# ESP32-XTonUINO.net
KiCad netlist of a schematic drawn in EAGLE
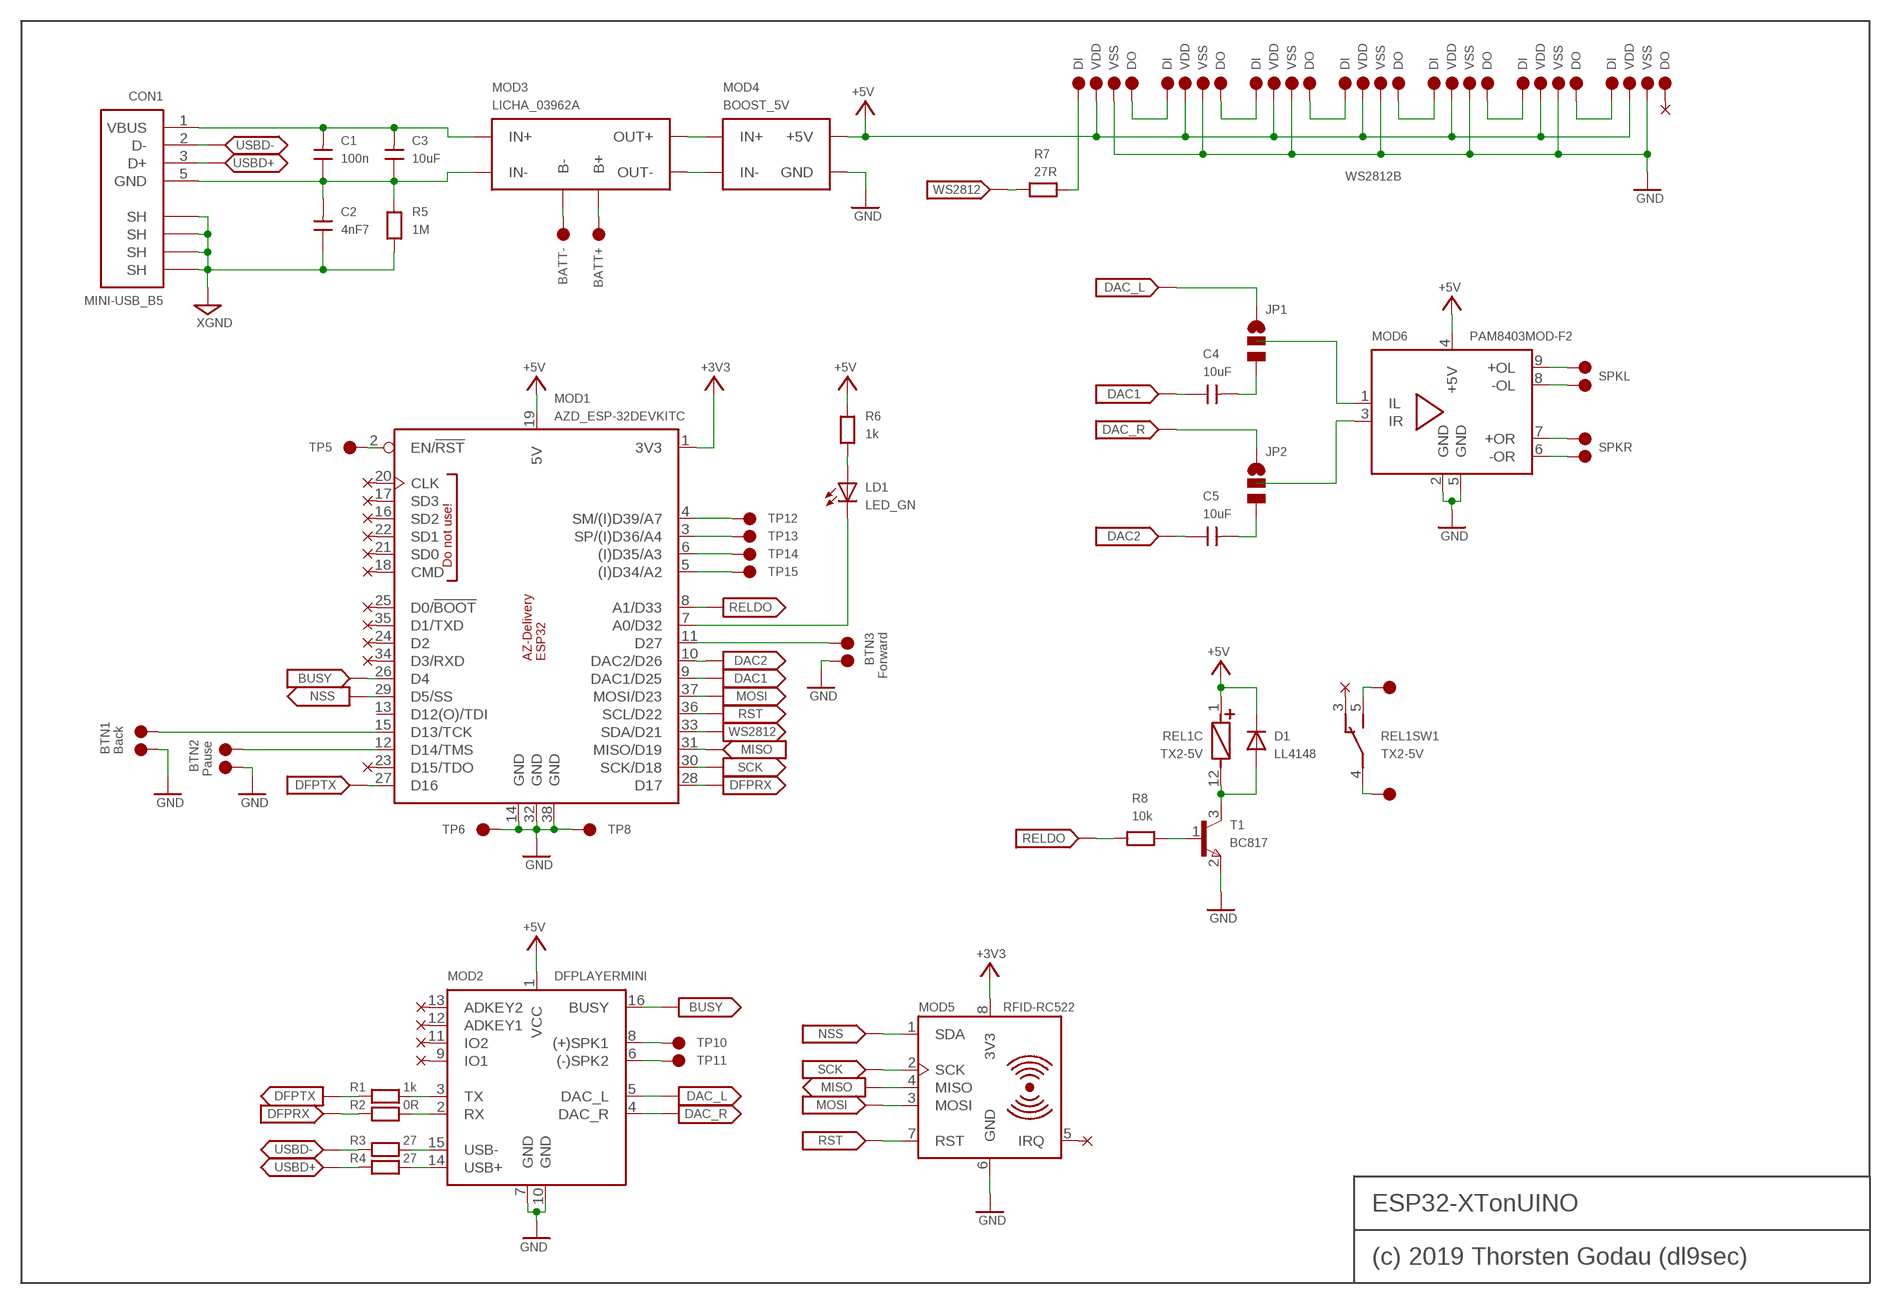
[diagram p0: schematic, sheet 1]

(export (version "E")
  (design (tool "Eeschema 10.0.6"))
  (components
    (comp (ref "C1")
      (value "100n")
      (footprint "eagle-import:0805")
      (libsource (lib "eagle-import") (part "C0805"))
    )
    (comp (ref "C2")
      (value "4nF7")
      (footprint "eagle-import:0805")
      (libsource (lib "eagle-import") (part "C0805"))
    )
    (comp (ref "C3")
      (value "10uF")
      (footprint "eagle-import:0805")
      (libsource (lib "eagle-import") (part "C0805"))
    )
    (comp (ref "C4")
      (value "10uF")
      (footprint "eagle-import:0805")
      (libsource (lib "eagle-import") (part "C0805"))
    )
    (comp (ref "C5")
      (value "10uF")
      (footprint "eagle-import:0805")
      (libsource (lib "eagle-import") (part "C0805"))
    )
    (comp (ref "CON1")
      (value "MINI-USB_B5")
      (footprint "eagle-import:MINIUSB_B5")
      (libsource (lib "eagle-import") (part "MINI-USB_B5"))
    )
    (comp (ref "D1")
      (value "LL4148")
      (footprint "eagle-import:MINIMELF")
      (libsource (lib "eagle-import") (part "LL4148"))
    )
    (comp (ref "JP1")
      (value "JUMPER_1X3SMD")
      (footprint "eagle-import:JUMPER_1X3_SMD")
      (libsource (lib "eagle-import") (part "JUMPER_1X3SMD"))
    )
    (comp (ref "JP2")
      (value "JUMPER_1X3SMD")
      (footprint "eagle-import:JUMPER_1X3_SMD")
      (libsource (lib "eagle-import") (part "JUMPER_1X3SMD"))
    )
    (comp (ref "LD1")
      (value "LED_GN")
      (footprint "eagle-import:LED3MMH")
      (libsource (lib "eagle-import") (part "LED_3MM_GN_H"))
    )
    (comp (ref "MOD1")
      (value "AZD_ESP-32DEVKITC")
      (footprint "eagle-import:AZD_ESP-32DEVKITC")
      (libsource (lib "eagle-import") (part "AZD_ESP-32DEVKITC"))
    )
    (comp (ref "MOD2")
      (value "DFPLAYERMINI")
      (footprint "eagle-import:DFPLAYERMINI")
      (libsource (lib "eagle-import") (part "DFPLAYERMINI"))
    )
    (comp (ref "MOD3")
      (value "LICHA_03962A")
      (footprint "eagle-import:LICHA_03962A")
      (libsource (lib "eagle-import") (part "LICHA_03962A"))
    )
    (comp (ref "MOD4")
      (value "BOOST_5V")
      (footprint "eagle-import:BOOST_5V")
      (libsource (lib "eagle-import") (part "BOOST_5V"))
    )
    (comp (ref "MOD5")
      (value "RFID-RC522")
      (footprint "eagle-import:RFID-RC522")
      (libsource (lib "eagle-import") (part "RFID-RC522"))
    )
    (comp (ref "MOD6")
      (value "PAM8403MOD-F2")
      (footprint "eagle-import:PAM8403MOD2")
      (libsource (lib "eagle-import") (part "PAM8403MOD-F2"))
    )
    (comp (ref "R1")
      (value "1k")
      (footprint "eagle-import:0805")
      (libsource (lib "eagle-import") (part "R0805"))
    )
    (comp (ref "R2")
      (value "0R")
      (footprint "eagle-import:0805")
      (libsource (lib "eagle-import") (part "R0805"))
    )
    (comp (ref "R3")
      (value "27")
      (footprint "eagle-import:0805")
      (libsource (lib "eagle-import") (part "R0805"))
    )
    (comp (ref "R4")
      (value "27")
      (footprint "eagle-import:0805")
      (libsource (lib "eagle-import") (part "R0805"))
    )
    (comp (ref "R5")
      (value "1M")
      (footprint "eagle-import:0805")
      (libsource (lib "eagle-import") (part "R0805"))
    )
    (comp (ref "R6")
      (value "1k")
      (footprint "eagle-import:0805")
      (libsource (lib "eagle-import") (part "R0805"))
    )
    (comp (ref "R7")
      (value "27R")
      (footprint "eagle-import:0805")
      (libsource (lib "eagle-import") (part "R0805"))
    )
    (comp (ref "R8")
      (value "10k")
      (footprint "eagle-import:0805")
      (libsource (lib "eagle-import") (part "R0805"))
    )
    (comp (ref "REL1")
      (value "TX2-5V")
      (footprint "eagle-import:RELTX2")
      (libsource (lib "eagle-import") (part "TX2-5V"))
    )
    (comp (ref "T1")
      (value "BC817")
      (footprint "eagle-import:SOT23")
      (libsource (lib "eagle-import") (part "BTUN"))
    )
    (comp (ref "TP1")
      (value "TESTPINTHT1")
      (footprint "eagle-import:TESTPIN_THT1")
      (libsource (lib "eagle-import") (part "TESTPINTHT1"))
    )
    (comp (ref "TP2")
      (value "TESTPINTHT1")
      (footprint "eagle-import:TESTPIN_THT1")
      (libsource (lib "eagle-import") (part "TESTPINTHT1"))
    )
    (comp (ref "TP3")
      (value "TESTPINTHT1")
      (footprint "eagle-import:TESTPIN_THT1")
      (libsource (lib "eagle-import") (part "TESTPINTHT1"))
    )
    (comp (ref "TP4")
      (value "TESTPINTHT1")
      (footprint "eagle-import:TESTPIN_THT1")
      (libsource (lib "eagle-import") (part "TESTPINTHT1"))
    )
    (comp (ref "TP5")
      (value "TESTPINTHT1")
      (footprint "eagle-import:TESTPIN_THT1")
      (libsource (lib "eagle-import") (part "TESTPINTHT1"))
    )
    (comp (ref "TP6")
      (value "TESTPINTHT1")
      (footprint "eagle-import:TESTPIN_THT1")
      (libsource (lib "eagle-import") (part "TESTPINTHT1"))
    )
    (comp (ref "TP7")
      (value "TESTPINTHT1")
      (footprint "eagle-import:TESTPIN_THT1")
      (libsource (lib "eagle-import") (part "TESTPINTHT1"))
    )
    (comp (ref "TP8")
      (value "TESTPINTHT1")
      (footprint "eagle-import:TESTPIN_THT1")
      (libsource (lib "eagle-import") (part "TESTPINTHT1"))
    )
    (comp (ref "TP9")
      (value "TESTPINTHT1")
      (footprint "eagle-import:TESTPIN_THT1")
      (libsource (lib "eagle-import") (part "TESTPINTHT1"))
    )
    (comp (ref "TP10")
      (value "TESTPINTHT2")
      (footprint "eagle-import:TESTPIN_THT2")
      (libsource (lib "eagle-import") (part "TESTPINTHT2"))
    )
    (comp (ref "TP11")
      (value "TESTPINTHT2")
      (footprint "eagle-import:TESTPIN_THT2")
      (libsource (lib "eagle-import") (part "TESTPINTHT2"))
    )
    (comp (ref "TP12")
      (value "TESTPINTHT1")
      (footprint "eagle-import:TESTPIN_THT1")
      (libsource (lib "eagle-import") (part "TESTPINTHT1"))
    )
    (comp (ref "TP13")
      (value "TESTPINTHT1")
      (footprint "eagle-import:TESTPIN_THT1")
      (libsource (lib "eagle-import") (part "TESTPINTHT1"))
    )
    (comp (ref "TP14")
      (value "TESTPINTHT1")
      (footprint "eagle-import:TESTPIN_THT1")
      (libsource (lib "eagle-import") (part "TESTPINTHT1"))
    )
    (comp (ref "TP15")
      (value "TESTPINTHT1")
      (footprint "eagle-import:TESTPIN_THT1")
      (libsource (lib "eagle-import") (part "TESTPINTHT1"))
    )
    (comp (ref "TP16")
      (value "TESTPINTHT1")
      (footprint "eagle-import:TESTPIN_THT1")
      (libsource (lib "eagle-import") (part "TESTPINTHT1"))
    )
    (comp (ref "TP17")
      (value "TESTPINTHT1")
      (footprint "eagle-import:TESTPIN_THT1")
      (libsource (lib "eagle-import") (part "TESTPINTHT1"))
    )
    (comp (ref "TP18")
      (value "TESTPINTHT1")
      (footprint "eagle-import:TESTPIN_THT1")
      (libsource (lib "eagle-import") (part "TESTPINTHT1"))
    )
    (comp (ref "TP19")
      (value "TESTPINTHT1")
      (footprint "eagle-import:TESTPIN_THT1")
      (libsource (lib "eagle-import") (part "TESTPINTHT1"))
    )
    (comp (ref "TP20")
      (value "TESTPINTHT1")
      (footprint "eagle-import:TESTPIN_THT1")
      (libsource (lib "eagle-import") (part "TESTPINTHT1"))
    )
    (comp (ref "TP21")
      (value "TESTPINTHT1")
      (footprint "eagle-import:TESTPIN_THT1")
      (libsource (lib "eagle-import") (part "TESTPINTHT1"))
    )
    (comp (ref "TP22")
      (value "TESTPINTHT1")
      (footprint "eagle-import:TESTPIN_THT1")
      (libsource (lib "eagle-import") (part "TESTPINTHT1"))
    )
    (comp (ref "TP23")
      (value "TESTPINTHT1")
      (footprint "eagle-import:TESTPIN_THT1")
      (libsource (lib "eagle-import") (part "TESTPINTHT1"))
    )
    (comp (ref "TP24")
      (value "TESTPINTHT1")
      (footprint "eagle-import:TESTPIN_THT1")
      (libsource (lib "eagle-import") (part "TESTPINTHT1"))
    )
    (comp (ref "TP25")
      (value "TESTPINTHT1")
      (footprint "eagle-import:TESTPIN_THT1")
      (libsource (lib "eagle-import") (part "TESTPINTHT1"))
    )
    (comp (ref "TP26")
      (value "TESTPINTHT1")
      (footprint "eagle-import:TESTPIN_THT1")
      (libsource (lib "eagle-import") (part "TESTPINTHT1"))
    )
    (comp (ref "TP27")
      (value "TESTPINTHT1")
      (footprint "eagle-import:TESTPIN_THT1")
      (libsource (lib "eagle-import") (part "TESTPINTHT1"))
    )
    (comp (ref "TP28")
      (value "TESTPINTHT1")
      (footprint "eagle-import:TESTPIN_THT1")
      (libsource (lib "eagle-import") (part "TESTPINTHT1"))
    )
    (comp (ref "TP29")
      (value "TESTPINTHT1")
      (footprint "eagle-import:TESTPIN_THT1")
      (libsource (lib "eagle-import") (part "TESTPINTHT1"))
    )
    (comp (ref "TP30")
      (value "TESTPINTHT1")
      (footprint "eagle-import:TESTPIN_THT1")
      (libsource (lib "eagle-import") (part "TESTPINTHT1"))
    )
    (comp (ref "TP31")
      (value "TESTPINTHT1")
      (footprint "eagle-import:TESTPIN_THT1")
      (libsource (lib "eagle-import") (part "TESTPINTHT1"))
    )
    (comp (ref "TP32")
      (value "TESTPINTHT1")
      (footprint "eagle-import:TESTPIN_THT1")
      (libsource (lib "eagle-import") (part "TESTPINTHT1"))
    )
    (comp (ref "TP33")
      (value "TESTPINTHT1")
      (footprint "eagle-import:TESTPIN_THT1")
      (libsource (lib "eagle-import") (part "TESTPINTHT1"))
    )
    (comp (ref "TP34")
      (value "TESTPINTHT1")
      (footprint "eagle-import:TESTPIN_THT1")
      (libsource (lib "eagle-import") (part "TESTPINTHT1"))
    )
    (comp (ref "TP35")
      (value "TESTPINTHT1")
      (footprint "eagle-import:TESTPIN_THT1")
      (libsource (lib "eagle-import") (part "TESTPINTHT1"))
    )
    (comp (ref "TP36")
      (value "TESTPINTHT1")
      (footprint "eagle-import:TESTPIN_THT1")
      (libsource (lib "eagle-import") (part "TESTPINTHT1"))
    )
    (comp (ref "TP37")
      (value "TESTPINTHT1")
      (footprint "eagle-import:TESTPIN_THT1")
      (libsource (lib "eagle-import") (part "TESTPINTHT1"))
    )
    (comp (ref "TP38")
      (value "TESTPINTHT1")
      (footprint "eagle-import:TESTPIN_THT1")
      (libsource (lib "eagle-import") (part "TESTPINTHT1"))
    )
    (comp (ref "TP39")
      (value "TESTPINTHT1")
      (footprint "eagle-import:TESTPIN_THT1")
      (libsource (lib "eagle-import") (part "TESTPINTHT1"))
    )
    (comp (ref "TP40")
      (value "TESTPINTHT1")
      (footprint "eagle-import:TESTPIN_THT1")
      (libsource (lib "eagle-import") (part "TESTPINTHT1"))
    )
    (comp (ref "TP41")
      (value "TESTPINTHT2")
      (footprint "eagle-import:TESTPIN_THT2")
      (libsource (lib "eagle-import") (part "TESTPINTHT2"))
    )
    (comp (ref "TP42")
      (value "TESTPINTHT2")
      (footprint "eagle-import:TESTPIN_THT2")
      (libsource (lib "eagle-import") (part "TESTPINTHT2"))
    )
    (comp (ref "TP43")
      (value "TESTPINTHT2")
      (footprint "eagle-import:TESTPIN_THT2")
      (libsource (lib "eagle-import") (part "TESTPINTHT2"))
    )
    (comp (ref "TP44")
      (value "TESTPINTHT2")
      (footprint "eagle-import:TESTPIN_THT2")
      (libsource (lib "eagle-import") (part "TESTPINTHT2"))
    )
    (comp (ref "TP45")
      (value "TESTPINTHT1")
      (footprint "eagle-import:TESTPIN_THT1")
      (libsource (lib "eagle-import") (part "TESTPINTHT1"))
    )
    (comp (ref "TP46")
      (value "TESTPINTHT2")
      (footprint "eagle-import:TESTPIN_THT2")
      (libsource (lib "eagle-import") (part "TESTPINTHT2"))
    )
    (comp (ref "TP47")
      (value "TESTPINTHT2")
      (footprint "eagle-import:TESTPIN_THT2")
      (libsource (lib "eagle-import") (part "TESTPINTHT2"))
    )
    (comp (ref "TP48")
      (value "TESTPINTHT1")
      (footprint "eagle-import:TESTPIN_THT1")
      (libsource (lib "eagle-import") (part "TESTPINTHT1"))
    )
    (comp (ref "TP49")
      (value "TESTPINTHT1")
      (footprint "eagle-import:TESTPIN_THT1")
      (libsource (lib "eagle-import") (part "TESTPINTHT1"))
    )
    (comp (ref "TP50")
      (value "TESTPINTHT1")
      (footprint "eagle-import:TESTPIN_THT1")
      (libsource (lib "eagle-import") (part "TESTPINTHT1"))
    )
    (comp (ref "TP51")
      (value "TESTPINTHT1")
      (footprint "eagle-import:TESTPIN_THT1")
      (libsource (lib "eagle-import") (part "TESTPINTHT1"))
    )
  )
  (nets
    (net (code "1") (name "+3V3") (class "Default")
      (node (ref "MOD1") (pin "1") (pinfunction "3V3_1") (pintype "passive"))
      (node (ref "MOD5") (pin "8") (pinfunction "3V3_8") (pintype "power_in"))
    )
    (net (code "2") (name "+5V") (class "Default")
      (node (ref "D1") (pin "K") (pinfunction "K_K") (pintype "passive"))
      (node (ref "MOD1") (pin "19") (pinfunction "5V_19") (pintype "power_in"))
      (node (ref "MOD2") (pin "1") (pinfunction "VCC_1") (pintype "power_in"))
      (node (ref "MOD4") (pin "+5V") (pinfunction "+5V_+5V") (pintype "power_in"))
      (node (ref "MOD6") (pin "4") (pinfunction "+5V_4") (pintype "power_in"))
      (node (ref "R6") (pin "2") (pinfunction "2_2") (pintype "passive"))
      (node (ref "REL1") (pin "1") (pinfunction "+_1") (pintype "power_in"))
      (node (ref "TP19") (pin "1") (pinfunction "TP_1") (pintype "passive"))
      (node (ref "TP23") (pin "1") (pinfunction "TP_1") (pintype "passive"))
      (node (ref "TP27") (pin "1") (pinfunction "TP_1") (pintype "passive"))
      (node (ref "TP31") (pin "1") (pinfunction "TP_1") (pintype "passive"))
      (node (ref "TP35") (pin "1") (pinfunction "TP_1") (pintype "passive"))
      (node (ref "TP39") (pin "1") (pinfunction "TP_1") (pintype "passive"))
      (node (ref "TP49") (pin "1") (pinfunction "TP_1") (pintype "passive"))
    )
    (net (code "3") (name "/BUSY") (class "Default")
      (node (ref "MOD1") (pin "26") (pinfunction "D4_26") (pintype "bidirectional"))
      (node (ref "MOD2") (pin "16") (pinfunction "BUSY_16") (pintype "passive"))
    )
    (net (code "4") (name "/DAC1") (class "Default")
      (node (ref "C4") (pin "1") (pinfunction "1_1") (pintype "passive"))
      (node (ref "MOD1") (pin "9") (pinfunction "DAC1/D25_9") (pintype "bidirectional"))
    )
    (net (code "5") (name "/DAC2") (class "Default")
      (node (ref "C5") (pin "1") (pinfunction "1_1") (pintype "passive"))
      (node (ref "MOD1") (pin "10") (pinfunction "DAC2/D26_10") (pintype "bidirectional"))
    )
    (net (code "6") (name "/DAC_L") (class "Default")
      (node (ref "JP1") (pin "1") (pinfunction "1_1") (pintype "passive"))
      (node (ref "MOD2") (pin "5") (pinfunction "DAC_L_5") (pintype "passive"))
    )
    (net (code "7") (name "/DAC_R") (class "Default")
      (node (ref "JP2") (pin "1") (pinfunction "1_1") (pintype "passive"))
      (node (ref "MOD2") (pin "4") (pinfunction "DAC_R_4") (pintype "passive"))
    )
    (net (code "8") (name "/DFPRX") (class "Default")
      (node (ref "MOD1") (pin "28") (pinfunction "D17_28") (pintype "bidirectional"))
      (node (ref "R2") (pin "1") (pinfunction "1_1") (pintype "passive"))
    )
    (net (code "9") (name "/DFPTX") (class "Default")
      (node (ref "MOD1") (pin "27") (pinfunction "D16_27") (pintype "bidirectional"))
      (node (ref "R1") (pin "1") (pinfunction "1_1") (pintype "passive"))
    )
    (net (code "10") (name "/MISO") (class "Default")
      (node (ref "MOD1") (pin "31") (pinfunction "MISO/D19_31") (pintype "bidirectional"))
      (node (ref "MOD5") (pin "4") (pinfunction "MISO_4") (pintype "passive"))
    )
    (net (code "11") (name "/MOSI") (class "Default")
      (node (ref "MOD1") (pin "37") (pinfunction "MOSI/D23_37") (pintype "bidirectional"))
      (node (ref "MOD5") (pin "3") (pinfunction "MOSI_3") (pintype "passive"))
    )
    (net (code "12") (name "/NSS") (class "Default")
      (node (ref "MOD1") (pin "29") (pinfunction "D5/SS_29") (pintype "bidirectional"))
      (node (ref "MOD5") (pin "1") (pinfunction "SDA_1") (pintype "passive"))
    )
    (net (code "13") (name "/RELDO") (class "Default")
      (node (ref "MOD1") (pin "8") (pinfunction "A1/D33_8") (pintype "bidirectional"))
      (node (ref "R8") (pin "1") (pinfunction "1_1") (pintype "passive"))
    )
    (net (code "14") (name "/RST") (class "Default")
      (node (ref "MOD1") (pin "36") (pinfunction "SCL/D22_36") (pintype "bidirectional"))
      (node (ref "MOD5") (pin "7") (pinfunction "RST_7") (pintype "passive"))
    )
    (net (code "15") (name "/SCK") (class "Default")
      (node (ref "MOD1") (pin "30") (pinfunction "SCK/D18_30") (pintype "bidirectional"))
      (node (ref "MOD5") (pin "2") (pinfunction "SCK_2") (pintype "passive"))
    )
    (net (code "16") (name "/USBD+") (class "Default")
      (node (ref "CON1") (pin "3") (pinfunction "D+_3") (pintype "bidirectional"))
      (node (ref "R4") (pin "1") (pinfunction "1_1") (pintype "passive"))
    )
    (net (code "17") (name "/USBD-") (class "Default")
      (node (ref "CON1") (pin "2") (pinfunction "D-_2") (pintype "bidirectional"))
      (node (ref "R3") (pin "1") (pinfunction "1_1") (pintype "passive"))
    )
    (net (code "18") (name "/WS2812") (class "Default")
      (node (ref "MOD1") (pin "33") (pinfunction "SDA/D21_33") (pintype "bidirectional"))
      (node (ref "R7") (pin "1") (pinfunction "1_1") (pintype "passive"))
    )
    (net (code "19") (name "GND") (class "Default")
      (node (ref "MOD1") (pin "14") (pinfunction "GND_14") (pintype "power_in"))
      (node (ref "MOD1") (pin "32") (pinfunction "GND_32") (pintype "power_in"))
      (node (ref "MOD1") (pin "38") (pinfunction "GND_38") (pintype "power_in"))
      (node (ref "MOD2") (pin "10") (pinfunction "GND_10") (pintype "power_in"))
      (node (ref "MOD2") (pin "7") (pinfunction "GND_7") (pintype "power_in"))
      (node (ref "MOD4") (pin "GND") (pinfunction "GND_GND") (pintype "passive"))
      (node (ref "MOD5") (pin "6") (pinfunction "GND_6") (pintype "power_in"))
      (node (ref "MOD6") (pin "2") (pinfunction "GND_2") (pintype "power_in"))
      (node (ref "MOD6") (pin "5") (pinfunction "GND_5") (pintype "power_in"))
      (node (ref "T1") (pin "2") (pinfunction "E_2") (pintype "passive"))
      (node (ref "TP17") (pin "1") (pinfunction "TP_1") (pintype "passive"))
      (node (ref "TP2") (pin "1") (pinfunction "TP_1") (pintype "passive"))
      (node (ref "TP20") (pin "1") (pinfunction "TP_1") (pintype "passive"))
      (node (ref "TP24") (pin "1") (pinfunction "TP_1") (pintype "passive"))
      (node (ref "TP28") (pin "1") (pinfunction "TP_1") (pintype "passive"))
      (node (ref "TP32") (pin "1") (pinfunction "TP_1") (pintype "passive"))
      (node (ref "TP36") (pin "1") (pinfunction "TP_1") (pintype "passive"))
      (node (ref "TP4") (pin "1") (pinfunction "TP_1") (pintype "passive"))
      (node (ref "TP40") (pin "1") (pinfunction "TP_1") (pintype "passive"))
      (node (ref "TP50") (pin "1") (pinfunction "TP_1") (pintype "passive"))
      (node (ref "TP6") (pin "1") (pinfunction "TP_1") (pintype "passive"))
      (node (ref "TP8") (pin "1") (pinfunction "TP_1") (pintype "passive"))
    )
    (net (code "20") (name "Net-(C4-Pad2)") (class "Default")
      (node (ref "C4") (pin "2") (pinfunction "2_2") (pintype "passive"))
      (node (ref "JP1") (pin "3") (pinfunction "3_3") (pintype "passive"))
    )
    (net (code "21") (name "Net-(C5-Pad2)") (class "Default")
      (node (ref "C5") (pin "2") (pinfunction "2_2") (pintype "passive"))
      (node (ref "JP2") (pin "3") (pinfunction "3_3") (pintype "passive"))
    )
    (net (code "22") (name "Net-(CON1-GND)") (class "Default")
      (node (ref "C1") (pin "1") (pinfunction "1_1") (pintype "passive"))
      (node (ref "C2") (pin "2") (pinfunction "2_2") (pintype "passive"))
      (node (ref "C3") (pin "1") (pinfunction "1_1") (pintype "passive"))
      (node (ref "CON1") (pin "5") (pinfunction "GND_5") (pintype "power_in"))
      (node (ref "MOD3") (pin "IN-") (pinfunction "IN-_IN-") (pintype "passive"))
      (node (ref "R5") (pin "2") (pinfunction "2_2") (pintype "passive"))
    )
    (net (code "23") (name "Net-(CON1-VBUS)") (class "Default")
      (node (ref "C1") (pin "2") (pinfunction "2_2") (pintype "passive"))
      (node (ref "C3") (pin "2") (pinfunction "2_2") (pintype "passive"))
      (node (ref "CON1") (pin "1") (pinfunction "VBUS_1") (pintype "power_in"))
      (node (ref "MOD3") (pin "IN+") (pinfunction "IN+_IN+") (pintype "passive"))
    )
    (net (code "24") (name "Net-(LD1-PadA)") (class "Default")
      (node (ref "LD1") (pin "A") (pinfunction "A_A") (pintype "passive"))
      (node (ref "R6") (pin "1") (pinfunction "1_1") (pintype "passive"))
    )
    (net (code "25") (name "Net-(MOD1-(I)D34{slash}A2)") (class "Default")
      (node (ref "MOD1") (pin "5") (pinfunction "(I)D34/A2_5") (pintype "input"))
      (node (ref "TP15") (pin "1") (pinfunction "TP_1") (pintype "passive"))
    )
    (net (code "26") (name "Net-(MOD1-(I)D35{slash}A3)") (class "Default")
      (node (ref "MOD1") (pin "6") (pinfunction "(I)D35/A3_6") (pintype "input"))
      (node (ref "TP14") (pin "1") (pinfunction "TP_1") (pintype "passive"))
    )
    (net (code "27") (name "Net-(MOD1-A0{slash}D32)") (class "Default")
      (node (ref "LD1") (pin "K") (pinfunction "K_K") (pintype "passive"))
      (node (ref "MOD1") (pin "7") (pinfunction "A0/D32_7") (pintype "bidirectional"))
    )
    (net (code "28") (name "Net-(MOD1-D13{slash}TCK)") (class "Default")
      (node (ref "MOD1") (pin "15") (pinfunction "D13/TCK_15") (pintype "bidirectional"))
      (node (ref "TP1") (pin "1") (pinfunction "TP_1") (pintype "passive"))
    )
    (net (code "29") (name "Net-(MOD1-D14{slash}TMS)") (class "Default")
      (node (ref "MOD1") (pin "12") (pinfunction "D14/TMS_12") (pintype "bidirectional"))
      (node (ref "TP3") (pin "1") (pinfunction "TP_1") (pintype "passive"))
    )
    (net (code "30") (name "Net-(MOD1-D27)") (class "Default")
      (node (ref "MOD1") (pin "11") (pinfunction "D27_11") (pintype "bidirectional"))
      (node (ref "TP16") (pin "1") (pinfunction "TP_1") (pintype "passive"))
    )
    (net (code "31") (name "Net-(MOD1-EN{slash}~{RST})") (class "Default")
      (node (ref "MOD1") (pin "2") (pinfunction "EN/~{RST}_2") (pintype "input"))
      (node (ref "TP5") (pin "1") (pinfunction "TP_1") (pintype "passive"))
    )
    (net (code "32") (name "Net-(MOD1-SM{slash}(I)D39{slash}A7)") (class "Default")
      (node (ref "MOD1") (pin "4") (pinfunction "SM/(I)D39/A7_4") (pintype "input"))
      (node (ref "TP12") (pin "1") (pinfunction "TP_1") (pintype "passive"))
    )
    (net (code "33") (name "Net-(MOD1-SP{slash}(I)D36{slash}A4)") (class "Default")
      (node (ref "MOD1") (pin "3") (pinfunction "SP/(I)D36/A4_3") (pintype "input"))
      (node (ref "TP13") (pin "1") (pinfunction "TP_1") (pintype "passive"))
    )
    (net (code "34") (name "Net-(MOD2-(+)SPK1)") (class "Default")
      (node (ref "MOD2") (pin "8") (pinfunction "(+)SPK1_8") (pintype "passive"))
      (node (ref "TP10") (pin "1") (pinfunction "TP_1") (pintype "passive"))
    )
    (net (code "35") (name "Net-(MOD2-(-)SPK2)") (class "Default")
      (node (ref "MOD2") (pin "6") (pinfunction "(-)SPK2_6") (pintype "passive"))
      (node (ref "TP11") (pin "1") (pinfunction "TP_1") (pintype "passive"))
    )
    (net (code "36") (name "Net-(MOD2-RX)") (class "Default")
      (node (ref "MOD2") (pin "2") (pinfunction "RX_2") (pintype "passive"))
      (node (ref "R2") (pin "2") (pinfunction "2_2") (pintype "passive"))
    )
    (net (code "37") (name "Net-(MOD2-TX)") (class "Default")
      (node (ref "MOD2") (pin "3") (pinfunction "TX_3") (pintype "passive"))
      (node (ref "R1") (pin "2") (pinfunction "2_2") (pintype "passive"))
    )
    (net (code "38") (name "Net-(MOD2-USB+)") (class "Default")
      (node (ref "MOD2") (pin "14") (pinfunction "USB+_14") (pintype "passive"))
      (node (ref "R4") (pin "2") (pinfunction "2_2") (pintype "passive"))
    )
    (net (code "39") (name "Net-(MOD2-USB-)") (class "Default")
      (node (ref "MOD2") (pin "15") (pinfunction "USB-_15") (pintype "passive"))
      (node (ref "R3") (pin "2") (pinfunction "2_2") (pintype "passive"))
    )
    (net (code "40") (name "Net-(MOD3-PadOUT+)") (class "Default")
      (node (ref "MOD3") (pin "OUT+") (pinfunction "OUT+_OUT+") (pintype "power_in"))
      (node (ref "MOD4") (pin "IN+") (pinfunction "IN+_IN+") (pintype "passive"))
    )
    (net (code "41") (name "Net-(MOD3-PadOUT-)") (class "Default")
      (node (ref "MOD3") (pin "OUT-") (pinfunction "OUT-_OUT-") (pintype "passive"))
      (node (ref "MOD4") (pin "IN-") (pinfunction "IN-_IN-") (pintype "passive"))
    )
    (net (code "42") (name "Net-(MOD6-+OL)") (class "Default")
      (node (ref "MOD6") (pin "9") (pinfunction "+OL_9") (pintype "passive"))
      (node (ref "TP41") (pin "1") (pinfunction "TP_1") (pintype "passive"))
    )
    (net (code "43") (name "Net-(MOD6-+OR)") (class "Default")
      (node (ref "MOD6") (pin "7") (pinfunction "+OR_7") (pintype "passive"))
      (node (ref "TP43") (pin "1") (pinfunction "TP_1") (pintype "passive"))
    )
    (net (code "44") (name "Net-(MOD6--OL)") (class "Default")
      (node (ref "MOD6") (pin "8") (pinfunction "-OL_8") (pintype "passive"))
      (node (ref "TP42") (pin "1") (pinfunction "TP_1") (pintype "passive"))
    )
    (net (code "45") (name "Net-(MOD6--OR)") (class "Default")
      (node (ref "MOD6") (pin "6") (pinfunction "-OR_6") (pintype "passive"))
      (node (ref "TP44") (pin "1") (pinfunction "TP_1") (pintype "passive"))
    )
    (net (code "46") (name "Net-(MOD6-IL)") (class "Default")
      (node (ref "JP1") (pin "2") (pinfunction "2_2") (pintype "passive"))
      (node (ref "MOD6") (pin "1") (pinfunction "IL_1") (pintype "passive"))
    )
    (net (code "47") (name "Net-(MOD6-IR)") (class "Default")
      (node (ref "JP2") (pin "2") (pinfunction "2_2") (pintype "passive"))
      (node (ref "MOD6") (pin "3") (pinfunction "IR_3") (pintype "passive"))
    )
    (net (code "48") (name "Net-(REL1A--)") (class "Default")
      (node (ref "D1") (pin "A") (pinfunction "A_A") (pintype "passive"))
      (node (ref "REL1") (pin "12") (pinfunction "-_12") (pintype "power_in"))
      (node (ref "T1") (pin "3") (pinfunction "C_3") (pintype "passive"))
    )
    (net (code "49") (name "Net-(REL1B-COM)") (class "Default")
      (node (ref "REL1") (pin "4") (pinfunction "COM_4") (pintype "passive"))
      (node (ref "TP47") (pin "1") (pinfunction "TP_1") (pintype "passive"))
    )
    (net (code "50") (name "Net-(REL1B-NO)") (class "Default")
      (node (ref "REL1") (pin "5") (pinfunction "NO_5") (pintype "passive"))
      (node (ref "TP46") (pin "1") (pinfunction "TP_1") (pintype "passive"))
    )
    (net (code "51") (name "Net-(T1-B)") (class "Default")
      (node (ref "R8") (pin "2") (pinfunction "2_2") (pintype "passive"))
      (node (ref "T1") (pin "1") (pinfunction "B_1") (pintype "passive"))
    )
    (net (code "52") (name "Net-(TP7-TP)") (class "Default")
      (node (ref "MOD3") (pin "B-") (pinfunction "B-_B-") (pintype "passive"))
      (node (ref "TP7") (pin "1") (pinfunction "TP_1") (pintype "passive"))
    )
    (net (code "53") (name "Net-(TP9-TP)") (class "Default")
      (node (ref "MOD3") (pin "B+") (pinfunction "B+_B+") (pintype "passive"))
      (node (ref "TP9") (pin "1") (pinfunction "TP_1") (pintype "passive"))
    )
    (net (code "54") (name "Net-(TP18-TP)") (class "Default")
      (node (ref "R7") (pin "2") (pinfunction "2_2") (pintype "passive"))
      (node (ref "TP18") (pin "1") (pinfunction "TP_1") (pintype "passive"))
    )
    (net (code "55") (name "Net-(TP21-TP)") (class "Default")
      (node (ref "TP21") (pin "1") (pinfunction "TP_1") (pintype "passive"))
      (node (ref "TP22") (pin "1") (pinfunction "TP_1") (pintype "passive"))
    )
    (net (code "56") (name "Net-(TP25-TP)") (class "Default")
      (node (ref "TP25") (pin "1") (pinfunction "TP_1") (pintype "passive"))
      (node (ref "TP26") (pin "1") (pinfunction "TP_1") (pintype "passive"))
    )
    (net (code "57") (name "Net-(TP29-TP)") (class "Default")
      (node (ref "TP29") (pin "1") (pinfunction "TP_1") (pintype "passive"))
      (node (ref "TP30") (pin "1") (pinfunction "TP_1") (pintype "passive"))
    )
    (net (code "58") (name "Net-(TP33-TP)") (class "Default")
      (node (ref "TP33") (pin "1") (pinfunction "TP_1") (pintype "passive"))
      (node (ref "TP34") (pin "1") (pinfunction "TP_1") (pintype "passive"))
    )
    (net (code "59") (name "Net-(TP37-TP)") (class "Default")
      (node (ref "TP37") (pin "1") (pinfunction "TP_1") (pintype "passive"))
      (node (ref "TP38") (pin "1") (pinfunction "TP_1") (pintype "passive"))
    )
    (net (code "60") (name "Net-(TP45-TP)") (class "Default")
      (node (ref "TP45") (pin "1") (pinfunction "TP_1") (pintype "passive"))
      (node (ref "TP48") (pin "1") (pinfunction "TP_1") (pintype "passive"))
    )
    (net (code "61") (name "XGND") (class "Default")
      (node (ref "C2") (pin "1") (pinfunction "1_1") (pintype "passive"))
      (node (ref "CON1") (pin "S1") (pinfunction "SH_S1") (pintype "passive"))
      (node (ref "CON1") (pin "S2") (pinfunction "SH_S2") (pintype "passive"))
      (node (ref "CON1") (pin "S3") (pinfunction "SH_S3") (pintype "passive"))
      (node (ref "CON1") (pin "S4") (pinfunction "SH_S4") (pintype "passive"))
      (node (ref "R5") (pin "1") (pinfunction "1_1") (pintype "passive"))
    )
    (net (code "62") (name "unconnected-(MOD1-CLK-Pad20)") (class "Default")
      (node (ref "MOD1") (pin "20") (pinfunction "CLK_20") (pintype "bidirectional"))
    )
    (net (code "63") (name "unconnected-(MOD1-CMD-Pad18)") (class "Default")
      (node (ref "MOD1") (pin "18") (pinfunction "CMD_18") (pintype "bidirectional"))
    )
    (net (code "64") (name "unconnected-(MOD1-D0{slash}~{BOOT}-Pad25)") (class "Default")
      (node (ref "MOD1") (pin "25") (pinfunction "D0/~{BOOT}_25") (pintype "bidirectional"))
    )
    (net (code "65") (name "unconnected-(MOD1-D1{slash}TXD-Pad35)") (class "Default")
      (node (ref "MOD1") (pin "35") (pinfunction "D1/TXD_35") (pintype "bidirectional"))
    )
    (net (code "66") (name "unconnected-(MOD1-D2-Pad24)") (class "Default")
      (node (ref "MOD1") (pin "24") (pinfunction "D2_24") (pintype "bidirectional"))
    )
    (net (code "67") (name "unconnected-(MOD1-D3{slash}RXD-Pad34)") (class "Default")
      (node (ref "MOD1") (pin "34") (pinfunction "D3/RXD_34") (pintype "bidirectional"))
    )
    (net (code "68") (name "unconnected-(MOD1-D12(O){slash}TDI-Pad13)") (class "Default")
      (node (ref "MOD1") (pin "13") (pinfunction "D12(O)/TDI_13") (pintype "bidirectional"))
    )
    (net (code "69") (name "unconnected-(MOD1-D15{slash}TDO-Pad23)") (class "Default")
      (node (ref "MOD1") (pin "23") (pinfunction "D15/TDO_23") (pintype "bidirectional"))
    )
    (net (code "70") (name "unconnected-(MOD1-SD0-Pad21)") (class "Default")
      (node (ref "MOD1") (pin "21") (pinfunction "SD0_21") (pintype "bidirectional"))
    )
    (net (code "71") (name "unconnected-(MOD1-SD1-Pad22)") (class "Default")
      (node (ref "MOD1") (pin "22") (pinfunction "SD1_22") (pintype "bidirectional"))
    )
    (net (code "72") (name "unconnected-(MOD1-SD2-Pad16)") (class "Default")
      (node (ref "MOD1") (pin "16") (pinfunction "SD2_16") (pintype "bidirectional"))
    )
    (net (code "73") (name "unconnected-(MOD1-SD3-Pad17)") (class "Default")
      (node (ref "MOD1") (pin "17") (pinfunction "SD3_17") (pintype "bidirectional"))
    )
    (net (code "74") (name "unconnected-(MOD2-ADKEY1-Pad12)") (class "Default")
      (node (ref "MOD2") (pin "12") (pinfunction "ADKEY1_12") (pintype "passive"))
    )
    (net (code "75") (name "unconnected-(MOD2-ADKEY2-Pad13)") (class "Default")
      (node (ref "MOD2") (pin "13") (pinfunction "ADKEY2_13") (pintype "passive"))
    )
    (net (code "76") (name "unconnected-(MOD2-IO1-Pad9)") (class "Default")
      (node (ref "MOD2") (pin "9") (pinfunction "IO1_9") (pintype "passive"))
    )
    (net (code "77") (name "unconnected-(MOD2-IO2-Pad11)") (class "Default")
      (node (ref "MOD2") (pin "11") (pinfunction "IO2_11") (pintype "passive"))
    )
    (net (code "78") (name "unconnected-(MOD5-IRQ-Pad5)") (class "Default")
      (node (ref "MOD5") (pin "5") (pinfunction "IRQ_5") (pintype "passive"))
    )
    (net (code "79") (name "unconnected-(REL1B-NC-Pad3)") (class "Default")
      (node (ref "REL1") (pin "3") (pinfunction "NC_3") (pintype "passive"))
    )
    (net (code "80") (name "unconnected-(TP51-TP-Pad1)") (class "Default")
      (node (ref "TP51") (pin "1") (pinfunction "TP_1") (pintype "passive"))
    )
  )
)
